# AIR.net
KiCad netlist of a schematic drawn in Altium Designer
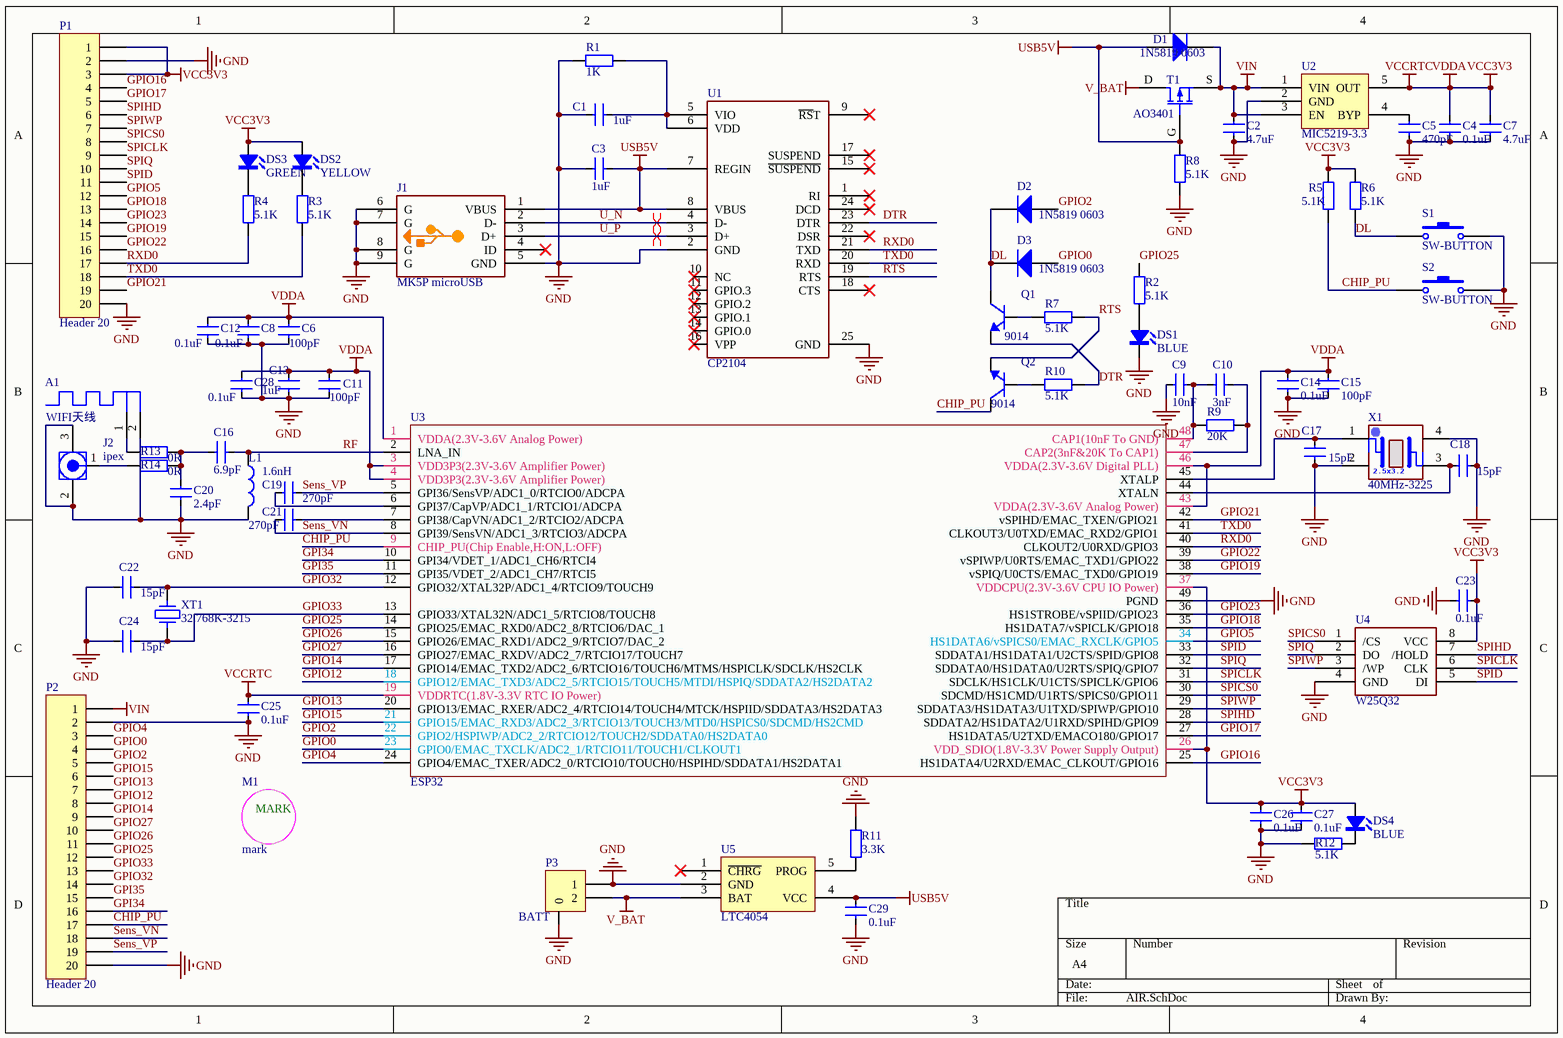
[diagram p0: AIR.SchDoc]

(export (version "E")
  (design (tool "Eeschema 10.0.6"))
  (components
    (comp (ref "A1") (value "WIFI天线") (footprint "2.4G") (libsource (lib "LIB_MANGO") (part "ANT2.4G")))
    (comp (ref "C1")
      (value "1uF")
      (footprint "C0402")
      (description "普通小电容")
      (libsource (lib "LIB_MANGO") (part "CAP"))
    )
    (comp (ref "C2")
      (value "4.7uF")
      (footprint "C0603")
      (description "普通小电容")
      (libsource (lib "LIB_MANGO") (part "CAP"))
    )
    (comp (ref "C3")
      (value "1uF")
      (footprint "C0402")
      (description "普通小电容")
      (libsource (lib "LIB_MANGO") (part "CAP"))
    )
    (comp (ref "C4")
      (value "0.1uF")
      (footprint "C0402")
      (description "普通小电容")
      (libsource (lib "LIB_MANGO") (part "CAP"))
    )
    (comp (ref "C5")
      (value "470pF")
      (footprint "C0402")
      (description "普通小电容")
      (libsource (lib "LIB_MANGO") (part "CAP"))
    )
    (comp (ref "C6")
      (value "100pF")
      (footprint "C0402")
      (description "普通小电容")
      (libsource (lib "LIB_MANGO") (part "CAP"))
    )
    (comp (ref "C7")
      (value "4.7uF")
      (footprint "C0603")
      (description "普通小电容")
      (libsource (lib "LIB_MANGO") (part "CAP"))
    )
    (comp (ref "C8")
      (value "0.1uF")
      (footprint "C0402")
      (description "普通小电容")
      (libsource (lib "LIB_MANGO") (part "CAP"))
    )
    (comp (ref "C9")
      (value "10nF")
      (footprint "C0402")
      (description "普通小电容")
      (libsource (lib "LIB_MANGO") (part "CAP"))
    )
    (comp (ref "C10")
      (value "3nF")
      (footprint "C0402")
      (description "普通小电容")
      (libsource (lib "LIB_MANGO") (part "CAP"))
    )
    (comp (ref "C11")
      (value "100pF")
      (footprint "C0402")
      (description "普通小电容")
      (libsource (lib "LIB_MANGO") (part "CAP"))
    )
    (comp (ref "C12")
      (value "0.1uF")
      (footprint "C0402")
      (description "普通小电容")
      (libsource (lib "LIB_MANGO") (part "CAP"))
    )
    (comp (ref "C13")
      (value "1uF")
      (footprint "C0402")
      (description "普通小电容")
      (libsource (lib "LIB_MANGO") (part "CAP"))
    )
    (comp (ref "C14")
      (value "0.1uF")
      (footprint "C0402")
      (description "普通小电容")
      (libsource (lib "LIB_MANGO") (part "CAP"))
    )
    (comp (ref "C15")
      (value "100pF")
      (footprint "C0402")
      (description "普通小电容")
      (libsource (lib "LIB_MANGO") (part "CAP"))
    )
    (comp (ref "C16")
      (value "6.9pF")
      (footprint "C0402")
      (description "射频电容")
      (libsource (lib "LIB_MANGO") (part "CAP"))
    )
    (comp (ref "C17")
      (value "15pF")
      (footprint "C0402")
      (description "普通小电容")
      (libsource (lib "LIB_MANGO") (part "CAP"))
    )
    (comp (ref "C18")
      (value "15pF")
      (footprint "C0402")
      (description "普通小电容")
      (libsource (lib "LIB_MANGO") (part "CAP"))
    )
    (comp (ref "C19")
      (value "270pF")
      (footprint "C0402")
      (description "普通小电容")
      (libsource (lib "LIB_MANGO") (part "CAP"))
    )
    (comp (ref "C20")
      (value "2.4pF")
      (footprint "C0402")
      (description "射频电容")
      (libsource (lib "LIB_MANGO") (part "CAP"))
    )
    (comp (ref "C21")
      (value "270pF")
      (footprint "C0402")
      (description "普通小电容")
      (libsource (lib "LIB_MANGO") (part "CAP"))
    )
    (comp (ref "C22")
      (value "15pF")
      (footprint "C0402")
      (description "普通小电容")
      (libsource (lib "LIB_MANGO") (part "CAP"))
    )
    (comp (ref "C23")
      (value "0.1uF")
      (footprint "C0402")
      (description "普通小电容")
      (libsource (lib "LIB_MANGO") (part "CAP"))
    )
    (comp (ref "C24")
      (value "15pF")
      (footprint "C0402")
      (description "普通小电容")
      (libsource (lib "LIB_MANGO") (part "CAP"))
    )
    (comp (ref "C25")
      (value "0.1uF")
      (footprint "C0402")
      (description "普通小电容")
      (libsource (lib "LIB_MANGO") (part "CAP"))
    )
    (comp (ref "C26")
      (value "0.1uF")
      (footprint "C0402")
      (description "普通小电容")
      (libsource (lib "LIB_MANGO") (part "CAP"))
    )
    (comp (ref "C27")
      (value "0.1uF")
      (footprint "C0402")
      (description "普通小电容")
      (libsource (lib "LIB_MANGO") (part "CAP"))
    )
    (comp (ref "C28")
      (value "0.1uF")
      (footprint "C0402")
      (description "普通小电容")
      (libsource (lib "LIB_MANGO") (part "CAP"))
    )
    (comp (ref "C29")
      (value "0.1uF")
      (footprint "C0402")
      (description "普通小电容")
      (libsource (lib "LIB_MANGO") (part "CAP"))
    )
    (comp (ref "D1")
      (value "1N5819 0603")
      (footprint "SOD523")
      (description "普通二极管")
      (libsource (lib "LIB_MANGO") (part "Diode"))
    )
    (comp (ref "D2")
      (value "1N5819 0603")
      (footprint "SOD523")
      (description "普通二极管")
      (libsource (lib "LIB_MANGO") (part "Diode"))
    )
    (comp (ref "D3")
      (value "1N5819 0603")
      (footprint "SOD523")
      (description "普通二极管")
      (libsource (lib "LIB_MANGO") (part "Diode"))
    )
    (comp (ref "DS1")
      (value "BLUE")
      (footprint "LED0402")
      (description "LED")
      (libsource (lib "LIB_MANGO") (part "LED"))
    )
    (comp (ref "DS2")
      (value "YELLOW")
      (footprint "LED0402")
      (description "LED")
      (libsource (lib "LIB_MANGO") (part "LED"))
    )
    (comp (ref "DS3")
      (value "GREEN")
      (footprint "LED0402")
      (description "LED")
      (libsource (lib "LIB_MANGO") (part "LED"))
    )
    (comp (ref "DS4")
      (value "BLUE")
      (footprint "LED0402")
      (description "LED")
      (libsource (lib "LIB_MANGO") (part "LED"))
    )
    (comp (ref "J1")
      (value "MK5P microUSB")
      (footprint "MICROUSB")
      (description "4固定脚microUSB座")
      (libsource (lib "A") (part "MICRO_USB"))
    )
    (comp (ref "J2")
      (value "ipex")
      (footprint "I-PEX SOCKET")
      (libsource (lib "LIB_MANGO") (part "MCX_IPEX"))
    )
    (comp (ref "L1")
      (value "1.6nH")
      (footprint "L0402")
      (description "射频电感")
      (libsource (lib "LIB_MANGO") (part "L0402"))
    )
    (comp (ref "M1") (value "mark") (footprint "ZY_UR-3X2") (libsource (lib "LIB_MANGO") (part "mark")))
    (comp (ref "P1")
      (value "Header 20")
      (footprint "HDR1X20-M")
      (description "Header, 20-Pin")
      (fields (field (name "PUBLISHER") "Altium Limited"))
      (libsource (lib "A") (part "Header 20"))
    )
    (comp (ref "P2")
      (value "Header 20")
      (footprint "HDR1X20-M")
      (description "Header, 20-Pin")
      (fields (field (name "PUBLISHER") "Altium Limited"))
      (libsource (lib "A") (part "Header 20"))
    )
    (comp (ref "P3")
      (value "BATT")
      (footprint "PH1.25-T")
      (description "Header, 4-Pin")
      (fields (field (name "PUBLISHER") "Altium Limited"))
      (libsource (lib "LIB_MANGO") (part "Header 2T"))
    )
    (comp (ref "Q1")
      (value "9014")
      (footprint "SOT23")
      (description "NPN三极管")
      (fields (field (name "PUBLISHER") "Altium Limited"))
      (libsource (lib "LIB_MANGO") (part "NPN"))
    )
    (comp (ref "Q2")
      (value "9014")
      (footprint "SOT23")
      (description "NPN三极管")
      (fields (field (name "PUBLISHER") "Altium Limited"))
      (libsource (lib "LIB_MANGO") (part "NPN"))
    )
    (comp (ref "R1")
      (value "1K")
      (footprint "R0402")
      (description "普通电阻")
      (libsource (lib "") (part "RES_2"))
    )
    (comp (ref "R2")
      (value "5.1K")
      (footprint "R0402")
      (description "普通电阻")
      (libsource (lib "LIB_MANGO") (part "RES"))
    )
    (comp (ref "R3")
      (value "5.1K")
      (footprint "R0402")
      (description "普通电阻")
      (libsource (lib "LIB_MANGO") (part "RES"))
    )
    (comp (ref "R4")
      (value "5.1K")
      (footprint "R0402")
      (description "普通电阻")
      (libsource (lib "LIB_MANGO") (part "RES"))
    )
    (comp (ref "R5")
      (value "5.1K")
      (footprint "R0402")
      (description "普通电阻")
      (libsource (lib "") (part "RES_3"))
    )
    (comp (ref "R6")
      (value "5.1K")
      (footprint "R0402")
      (description "普通电阻")
      (libsource (lib "LIB_MANGO") (part "RES"))
    )
    (comp (ref "R7")
      (value "5.1K")
      (footprint "R0402")
      (description "普通电阻")
      (libsource (lib "") (part "RES_1"))
    )
    (comp (ref "R8")
      (value "5.1K")
      (footprint "R0402")
      (description "普通电阻")
      (libsource (lib "LIB_MANGO") (part "RES"))
    )
    (comp (ref "R9")
      (value "20K")
      (footprint "R0402")
      (description "普通电阻")
      (libsource (lib "") (part "RES_1"))
    )
    (comp (ref "R10")
      (value "5.1K")
      (footprint "R0402")
      (description "普通电阻")
      (libsource (lib "") (part "RES_1"))
    )
    (comp (ref "R11")
      (value "3.3K")
      (footprint "R0402")
      (description "普通电阻")
      (libsource (lib "LIB_MANGO") (part "RES"))
    )
    (comp (ref "R12")
      (value "5.1K")
      (footprint "R0402")
      (description "普通电阻")
      (libsource (lib "") (part "RES_1"))
    )
    (comp (ref "R13")
      (value "0R")
      (footprint "R0402")
      (description "普通电阻")
      (libsource (lib "") (part "RES_1"))
    )
    (comp (ref "R14")
      (value "0R")
      (footprint "R0402")
      (description "普通电阻")
      (libsource (lib "") (part "RES_1"))
    )
    (comp (ref "S1")
      (value "SW-BUTTON")
      (footprint "MINIBUTTON")
      (libsource (lib "LIB_MANGO") (part "SW-BUTTON"))
    )
    (comp (ref "S2")
      (value "SW-BUTTON")
      (footprint "MINIBUTTON")
      (libsource (lib "LIB_MANGO") (part "SW-BUTTON"))
    )
    (comp (ref "T1") (value "AO3401") (footprint "SOT23") (libsource (lib "LIB_MANGO") (part "MOS-P")))
    (comp (ref "U1") (value "CP2104") (footprint "QFN24") (libsource (lib "LIB_MANGO") (part "CP2104")))
    (comp (ref "U2")
      (value "MIC5219-3.3")
      (footprint "SOT23-5")
      (libsource (lib "LIB_MANGO") (part "MIC5219"))
    )
    (comp (ref "U3") (value "ESP32") (footprint "QFN40P600X600X100-48N") (libsource (lib "A") (part "ESP32")))
    (comp (ref "U4")
      (value "W25Q32")
      (footprint "WSON-SPIFLASH")
      (libsource (lib "LIB_MANGO") (part "SPIFLASH_SOP8W"))
    )
    (comp (ref "U5")
      (value "LTC4054")
      (footprint "SOT23-5")
      (description "锂电池管理芯片")
      (libsource (lib "LIB_MANGO") (part "LTC4054"))
    )
    (comp (ref "X1")
      (value "40MHz-3225")
      (footprint "XTAL3225")
      (libsource (lib "LIB_MANGO") (part "XTAL3225"))
    )
    (comp (ref "XT1")
      (value "32.768K-3215")
      (footprint "Y3215")
      (description "晶振")
      (libsource (lib "LIB_MANGO") (part "XT"))
    )
  )
  (nets
    (net (code "1") (name "/CHIP_PU") (class "Default")
      (node (ref "P2") (pin "17") (pinfunction "17_17") (pintype "passive"))
      (node (ref "Q2") (pin "C") (pinfunction "C_C") (pintype "passive"))
      (node (ref "R5") (pin "2") (pinfunction "2_2") (pintype "passive"))
      (node (ref "S2") (pin "1") (pinfunction "1_1") (pintype "passive"))
      (node (ref "U3") (pin "9") (pinfunction "CHIP_PU(Chip_Enable,H:ON,L:OFF)_9") (pintype "passive"))
    )
    (net (code "2") (name "/DL") (class "Default")
      (node (ref "D2") (pin "K") (pinfunction "K_K") (pintype "passive"))
      (node (ref "D3") (pin "K") (pinfunction "K_K") (pintype "passive"))
      (node (ref "Q1") (pin "C") (pinfunction "C_C") (pintype "passive"))
      (node (ref "R6") (pin "1") (pinfunction "1_1") (pintype "passive"))
      (node (ref "S1") (pin "1") (pinfunction "1_1") (pintype "passive"))
    )
    (net (code "3") (name "/DTR") (class "Default")
      (node (ref "Q1") (pin "E") (pinfunction "E_E") (pintype "passive"))
      (node (ref "R10") (pin "1") (pinfunction "1_1") (pintype "passive"))
      (node (ref "U1") (pin "23") (pinfunction "DTR_23") (pintype "passive"))
    )
    (net (code "4") (name "/GPI34") (class "Default")
      (node (ref "P2") (pin "16") (pinfunction "16_16") (pintype "passive"))
      (node (ref "U3") (pin "10") (pinfunction "GPI34/VDET_1/ADC1_CH6/RTCI4_10") (pintype "passive"))
    )
    (net (code "5") (name "/GPI35") (class "Default")
      (node (ref "P2") (pin "15") (pinfunction "15_15") (pintype "passive"))
      (node (ref "U3") (pin "11") (pinfunction "GPI35/VDET_2/ADC1_CH7/RTCI5_11") (pintype "passive"))
    )
    (net (code "6") (name "/GPIO0") (class "Default")
      (node (ref "D3") (pin "A") (pinfunction "A_A") (pintype "passive"))
      (node (ref "P2") (pin "4") (pinfunction "4_4") (pintype "passive"))
      (node (ref "U3") (pin "23") (pinfunction "GPIO0/EMAC_TXCLK/ADC2_1/RTCIO11/TOUCH1/CLKOUT1_23") (pintype "passive"))
    )
    (net (code "7") (name "/GPIO2") (class "Default")
      (node (ref "D2") (pin "A") (pinfunction "A_A") (pintype "passive"))
      (node (ref "P2") (pin "5") (pinfunction "5_5") (pintype "passive"))
      (node (ref "U3") (pin "22") (pinfunction "GPIO2/HSPIWP/ADC2_2/RTCIO12/TOUCH2/SDDATA0/HS2DATA0_22") (pintype "passive"))
    )
    (net (code "8") (name "/GPIO4") (class "Default")
      (node (ref "P2") (pin "3") (pinfunction "3_3") (pintype "passive"))
      (node (ref "U3") (pin "24") (pinfunction "GPIO4/EMAC_TXER/ADC2_0/RTCIO10/TOUCH0/HSPIHD/SDDATA1/HS2DATA1_24") (pintype "passive"))
    )
    (net (code "9") (name "/GPIO5") (class "Default")
      (node (ref "P1") (pin "12") (pinfunction "12_12") (pintype "passive"))
      (node (ref "U3") (pin "34") (pinfunction "HS1DATA6/vSPICS0/EMAC_RXCLK/GPIO5_34") (pintype "passive"))
    )
    (net (code "10") (name "/GPIO12") (class "Default")
      (node (ref "P2") (pin "8") (pinfunction "8_8") (pintype "passive"))
      (node (ref "U3") (pin "18") (pinfunction "GPIO12/EMAC_TXD3/ADC2_5/RTCIO15/TOUCH5/MTDI/HSPIQ/SDDATA2/HS2DATA2_18") (pintype "passive"))
    )
    (net (code "11") (name "/GPIO13") (class "Default")
      (node (ref "P2") (pin "7") (pinfunction "7_7") (pintype "passive"))
      (node (ref "U3") (pin "20") (pinfunction "GPIO13/EMAC_RXER/ADC2_4/RTCIO14/TOUCH4/MTCK/HSPIID/SDDATA3/HS2DATA3_20") (pintype "passive"))
    )
    (net (code "12") (name "/GPIO14") (class "Default")
      (node (ref "P2") (pin "9") (pinfunction "9_9") (pintype "passive"))
      (node (ref "U3") (pin "17") (pinfunction "GPIO14/EMAC_TXD2/ADC2_6/RTCIO16/TOUCH6/MTMS/HSPICLK/SDCLK/HS2CLK_17") (pintype "passive"))
    )
    (net (code "13") (name "/GPIO15") (class "Default")
      (node (ref "P2") (pin "6") (pinfunction "6_6") (pintype "passive"))
      (node (ref "U3") (pin "21") (pinfunction "GPIO15/EMAC_RXD3/ADC2_3/RTCIO13/TOUCH3/MTD0/HSPICS0/SDCMD/HS2CMD_21") (pintype "passive"))
    )
    (net (code "14") (name "/GPIO16") (class "Default")
      (node (ref "P1") (pin "4") (pinfunction "4_4") (pintype "passive"))
      (node (ref "U3") (pin "25") (pinfunction "HS1DATA4/U2RXD/EMAC_CLKOUT/GPIO16_25") (pintype "passive"))
    )
    (net (code "15") (name "/GPIO17") (class "Default")
      (node (ref "P1") (pin "5") (pinfunction "5_5") (pintype "passive"))
      (node (ref "U3") (pin "27") (pinfunction "HS1DATA5/U2TXD/EMACO180/GPIO17_27") (pintype "passive"))
    )
    (net (code "16") (name "/GPIO18") (class "Default")
      (node (ref "P1") (pin "13") (pinfunction "13_13") (pintype "passive"))
      (node (ref "U3") (pin "35") (pinfunction "HS1DATA7/vSPICLK/GPIO18_35") (pintype "passive"))
    )
    (net (code "17") (name "/GPIO19") (class "Default")
      (node (ref "P1") (pin "15") (pinfunction "15_15") (pintype "passive"))
      (node (ref "U3") (pin "38") (pinfunction "vSPIQ/U0CTS/EMAC_TXD0/GPIO19_38") (pintype "passive"))
    )
    (net (code "18") (name "/GPIO21") (class "Default")
      (node (ref "P1") (pin "19") (pinfunction "19_19") (pintype "passive"))
      (node (ref "U3") (pin "42") (pinfunction "vSPIHD/EMAC_TXEN/GPIO21_42") (pintype "passive"))
    )
    (net (code "19") (name "/GPIO22") (class "Default")
      (node (ref "P1") (pin "16") (pinfunction "16_16") (pintype "passive"))
      (node (ref "U3") (pin "39") (pinfunction "vSPIWP/U0RTS/EMAC_TXD1/GPIO22_39") (pintype "passive"))
    )
    (net (code "20") (name "/GPIO23") (class "Default")
      (node (ref "P1") (pin "14") (pinfunction "14_14") (pintype "passive"))
      (node (ref "U3") (pin "36") (pinfunction "HS1STROBE/vSPIID/GPIO23_36") (pintype "passive"))
    )
    (net (code "21") (name "/GPIO25") (class "Default")
      (node (ref "P2") (pin "12") (pinfunction "12_12") (pintype "passive"))
      (node (ref "R2") (pin "2") (pinfunction "2_2") (pintype "passive"))
      (node (ref "U3") (pin "14") (pinfunction "GPIO25/EMAC_RXD0/ADC2_8/RTCIO6/DAC_1_14") (pintype "passive"))
    )
    (net (code "22") (name "/GPIO26") (class "Default")
      (node (ref "P2") (pin "11") (pinfunction "11_11") (pintype "passive"))
      (node (ref "U3") (pin "15") (pinfunction "GPIO26/EMAC_RXD1/ADC2_9/RTCIO7/DAC_2_15") (pintype "passive"))
    )
    (net (code "23") (name "/GPIO27") (class "Default")
      (node (ref "P2") (pin "10") (pinfunction "10_10") (pintype "passive"))
      (node (ref "U3") (pin "16") (pinfunction "GPIO27/EMAC_RXDV/ADC2_7/RTCIO17/TOUCH7_16") (pintype "passive"))
    )
    (net (code "24") (name "/GPIO32") (class "Default")
      (node (ref "C22") (pin "2") (pinfunction "2_2") (pintype "passive"))
      (node (ref "P2") (pin "14") (pinfunction "14_14") (pintype "passive"))
      (node (ref "U3") (pin "12") (pinfunction "GPIO32/XTAL32P/ADC1_4/RTCIO9/TOUCH9_12") (pintype "passive"))
      (node (ref "XT1") (pin "2") (pinfunction "2_2") (pintype "passive"))
    )
    (net (code "25") (name "/GPIO33") (class "Default")
      (node (ref "C24") (pin "2") (pinfunction "2_2") (pintype "passive"))
      (node (ref "P2") (pin "13") (pinfunction "13_13") (pintype "passive"))
      (node (ref "U3") (pin "13") (pinfunction "GPIO33/XTAL32N/ADC1_5/RTCIO8/TOUCH8_13") (pintype "passive"))
      (node (ref "XT1") (pin "1") (pinfunction "1_1") (pintype "passive"))
    )
    (net (code "26") (name "/RF") (class "Default")
      (node (ref "C16") (pin "2") (pinfunction "2_2") (pintype "passive"))
      (node (ref "L1") (pin "2") (pinfunction "2_2") (pintype "passive"))
      (node (ref "U3") (pin "2") (pinfunction "LNA_IN_2") (pintype "passive"))
    )
    (net (code "27") (name "/RTS") (class "Default")
      (node (ref "Q2") (pin "E") (pinfunction "E_E") (pintype "passive"))
      (node (ref "R7") (pin "1") (pinfunction "1_1") (pintype "passive"))
      (node (ref "U1") (pin "19") (pinfunction "RTS_19") (pintype "passive"))
    )
    (net (code "28") (name "/RXD0") (class "Default")
      (node (ref "P1") (pin "17") (pinfunction "17_17") (pintype "passive"))
      (node (ref "R4") (pin "1") (pinfunction "1_1") (pintype "passive"))
      (node (ref "U1") (pin "21") (pinfunction "TXD_21") (pintype "passive"))
      (node (ref "U3") (pin "40") (pinfunction "CLKOUT2/U0RXD/GPIO3_40") (pintype "passive"))
    )
    (net (code "29") (name "/SPICLK") (class "Default")
      (node (ref "P1") (pin "9") (pinfunction "9_9") (pintype "passive"))
      (node (ref "U3") (pin "31") (pinfunction "SDCLK/HS1CLK/U1CTS/SPICLK/GPIO6_31") (pintype "passive"))
      (node (ref "U4") (pin "6") (pinfunction "CLK_6") (pintype "passive"))
    )
    (net (code "30") (name "/SPICS0") (class "Default")
      (node (ref "P1") (pin "8") (pinfunction "8_8") (pintype "passive"))
      (node (ref "U3") (pin "30") (pinfunction "SDCMD/HS1CMD/U1RTS/SPICS0/GPIO11_30") (pintype "passive"))
      (node (ref "U4") (pin "1") (pinfunction "/CS_1") (pintype "passive"))
    )
    (net (code "31") (name "/SPID") (class "Default")
      (node (ref "P1") (pin "11") (pinfunction "11_11") (pintype "passive"))
      (node (ref "U3") (pin "33") (pinfunction "SDDATA1/HS1DATA1/U2CTS/SPID/GPIO8_33") (pintype "passive"))
      (node (ref "U4") (pin "5") (pinfunction "DI_5") (pintype "passive"))
    )
    (net (code "32") (name "/SPIHD") (class "Default")
      (node (ref "P1") (pin "6") (pinfunction "6_6") (pintype "passive"))
      (node (ref "U3") (pin "28") (pinfunction "SDDATA2/HS1DATA2/U1RXD/SPIHD/GPIO9_28") (pintype "passive"))
      (node (ref "U4") (pin "7") (pinfunction "/HOLD_7") (pintype "passive"))
    )
    (net (code "33") (name "/SPIQ") (class "Default")
      (node (ref "P1") (pin "10") (pinfunction "10_10") (pintype "passive"))
      (node (ref "U3") (pin "32") (pinfunction "SDDATA0/HS1DATA0/U2RTS/SPIQ/GPIO7_32") (pintype "passive"))
      (node (ref "U4") (pin "2") (pinfunction "DO_2") (pintype "passive"))
    )
    (net (code "34") (name "/SPIWP") (class "Default")
      (node (ref "P1") (pin "7") (pinfunction "7_7") (pintype "passive"))
      (node (ref "U3") (pin "29") (pinfunction "SDDATA3/HS1DATA3/U1TXD/SPIWP/GPIO10_29") (pintype "passive"))
      (node (ref "U4") (pin "3") (pinfunction "/WP_3") (pintype "passive"))
    )
    (net (code "35") (name "/Sens_VN") (class "Default")
      (node (ref "C21") (pin "1") (pinfunction "1_1") (pintype "passive"))
      (node (ref "P2") (pin "18") (pinfunction "18_18") (pintype "passive"))
      (node (ref "U3") (pin "8") (pinfunction "GPI39/SensVN/ADC1_3/RTCIO3/ADCPA_8") (pintype "passive"))
    )
    (net (code "36") (name "/Sens_VP") (class "Default")
      (node (ref "C19") (pin "2") (pinfunction "2_2") (pintype "passive"))
      (node (ref "P2") (pin "19") (pinfunction "19_19") (pintype "passive"))
      (node (ref "U3") (pin "5") (pinfunction "GPI36/SensVP/ADC1_0/RTCIO0/ADCPA_5") (pintype "passive"))
    )
    (net (code "37") (name "/TXD0") (class "Default")
      (node (ref "P1") (pin "18") (pinfunction "18_18") (pintype "passive"))
      (node (ref "R3") (pin "1") (pinfunction "1_1") (pintype "passive"))
      (node (ref "U1") (pin "20") (pinfunction "RXD_20") (pintype "passive"))
      (node (ref "U3") (pin "41") (pinfunction "CLKOUT3/U0TXD/EMAC_RXD2/GPIO1_41") (pintype "passive"))
    )
    (net (code "38") (name "/U_N") (class "Default")
      (node (ref "J1") (pin "2") (pinfunction "D-_2") (pintype "passive"))
      (node (ref "U1") (pin "4") (pinfunction "D-_4") (pintype "passive"))
    )
    (net (code "39") (name "/U_P") (class "Default")
      (node (ref "J1") (pin "3") (pinfunction "D+_3") (pintype "passive"))
      (node (ref "U1") (pin "3") (pinfunction "D+_3") (pintype "passive"))
    )
    (net (code "40") (name "GND") (class "Default")
      (node (ref "A1") (pin "2") (pinfunction "G_2") (pintype "passive"))
      (node (ref "C1") (pin "2") (pinfunction "2_2") (pintype "passive"))
      (node (ref "C11") (pin "1") (pinfunction "1_1") (pintype "passive"))
      (node (ref "C12") (pin "1") (pinfunction "1_1") (pintype "passive"))
      (node (ref "C13") (pin "1") (pinfunction "1_1") (pintype "passive"))
      (node (ref "C14") (pin "1") (pinfunction "1_1") (pintype "passive"))
      (node (ref "C15") (pin "1") (pinfunction "1_1") (pintype "passive"))
      (node (ref "C17") (pin "2") (pinfunction "2_2") (pintype "passive"))
      (node (ref "C18") (pin "2") (pinfunction "2_2") (pintype "passive"))
      (node (ref "C2") (pin "1") (pinfunction "1_1") (pintype "passive"))
      (node (ref "C20") (pin "1") (pinfunction "1_1") (pintype "passive"))
      (node (ref "C22") (pin "1") (pinfunction "1_1") (pintype "passive"))
      (node (ref "C23") (pin "2") (pinfunction "2_2") (pintype "passive"))
      (node (ref "C24") (pin "1") (pinfunction "1_1") (pintype "passive"))
      (node (ref "C25") (pin "1") (pinfunction "1_1") (pintype "passive"))
      (node (ref "C26") (pin "1") (pinfunction "1_1") (pintype "passive"))
      (node (ref "C27") (pin "1") (pinfunction "1_1") (pintype "passive"))
      (node (ref "C28") (pin "1") (pinfunction "1_1") (pintype "passive"))
      (node (ref "C29") (pin "1") (pinfunction "1_1") (pintype "passive"))
      (node (ref "C3") (pin "1") (pinfunction "1_1") (pintype "passive"))
      (node (ref "C4") (pin "1") (pinfunction "1_1") (pintype "passive"))
      (node (ref "C5") (pin "2") (pinfunction "2_2") (pintype "passive"))
      (node (ref "C6") (pin "1") (pinfunction "1_1") (pintype "passive"))
      (node (ref "C7") (pin "1") (pinfunction "1_1") (pintype "passive"))
      (node (ref "C8") (pin "1") (pinfunction "1_1") (pintype "passive"))
      (node (ref "C9") (pin "2") (pinfunction "2_2") (pintype "passive"))
      (node (ref "DS1") (pin "K") (pinfunction "2_K") (pintype "passive"))
      (node (ref "J1") (pin "5") (pinfunction "GND_5") (pintype "power_in"))
      (node (ref "J1") (pin "6") (pinfunction "G_6") (pintype "passive"))
      (node (ref "J1") (pin "7") (pinfunction "G_7") (pintype "passive"))
      (node (ref "J1") (pin "8") (pinfunction "G_8") (pintype "passive"))
      (node (ref "J1") (pin "9") (pinfunction "G_9") (pintype "passive"))
      (node (ref "J2") (pin "2") (pinfunction "GND_2") (pintype "power_in"))
      (node (ref "J2") (pin "3") (pinfunction "GND_3") (pintype "power_in"))
      (node (ref "L1") (pin "1") (pinfunction "1_1") (pintype "passive"))
      (node (ref "P1") (pin "2") (pinfunction "2_2") (pintype "passive"))
      (node (ref "P1") (pin "20") (pinfunction "20_20") (pintype "passive"))
      (node (ref "P2") (pin "2") (pinfunction "2_2") (pintype "passive"))
      (node (ref "P2") (pin "20") (pinfunction "20_20") (pintype "passive"))
      (node (ref "P3") (pin "0") (pinfunction "0_0") (pintype "passive"))
      (node (ref "P3") (pin "1") (pinfunction "1_1") (pintype "passive"))
      (node (ref "R1") (pin "1") (pinfunction "1_1") (pintype "passive"))
      (node (ref "R11") (pin "2") (pinfunction "2_2") (pintype "passive"))
      (node (ref "R12") (pin "2") (pinfunction "2_2") (pintype "passive"))
      (node (ref "R8") (pin "1") (pinfunction "1_1") (pintype "passive"))
      (node (ref "S1") (pin "2") (pinfunction "2_2") (pintype "passive"))
      (node (ref "S2") (pin "2") (pinfunction "2_2") (pintype "passive"))
      (node (ref "U1") (pin "2") (pinfunction "GND_2") (pintype "power_in"))
      (node (ref "U1") (pin "25") (pinfunction "GND_25") (pintype "power_in"))
      (node (ref "U2") (pin "2") (pinfunction "GND_2") (pintype "passive"))
      (node (ref "U3") (pin "49") (pinfunction "PGND_49") (pintype "passive"))
      (node (ref "U4") (pin "4") (pinfunction "GND_4") (pintype "passive"))
      (node (ref "U5") (pin "2") (pinfunction "GND_2") (pintype "passive"))
      (node (ref "X1") (pin "2") (pinfunction "NC1_2") (pintype "passive"))
      (node (ref "X1") (pin "4") (pinfunction "NC2_4") (pintype "passive"))
    )
    (net (code "41") (name "Net-(A1-Pad1)") (class "Default")
      (node (ref "A1") (pin "1") (pintype "passive"))
      (node (ref "R13") (pin "2") (pinfunction "2_2") (pintype "passive"))
    )
    (net (code "42") (name "Net-(C16-Pad1)") (class "Default")
      (node (ref "C16") (pin "1") (pinfunction "1_1") (pintype "passive"))
      (node (ref "C20") (pin "2") (pinfunction "2_2") (pintype "passive"))
      (node (ref "R13") (pin "1") (pinfunction "1_1") (pintype "passive"))
      (node (ref "R14") (pin "1") (pinfunction "1_1") (pintype "passive"))
    )
    (net (code "43") (name "Net-(DS1-1)") (class "Default")
      (node (ref "DS1") (pin "A") (pinfunction "1_A") (pintype "passive"))
      (node (ref "R2") (pin "1") (pinfunction "1_1") (pintype "passive"))
    )
    (net (code "44") (name "Net-(DS2-2)") (class "Default")
      (node (ref "DS2") (pin "K") (pinfunction "2_K") (pintype "passive"))
      (node (ref "R3") (pin "2") (pinfunction "2_2") (pintype "passive"))
    )
    (net (code "45") (name "Net-(DS3-2)") (class "Default")
      (node (ref "DS3") (pin "K") (pinfunction "2_K") (pintype "passive"))
      (node (ref "R4") (pin "2") (pinfunction "2_2") (pintype "passive"))
    )
    (net (code "46") (name "Net-(DS4-2)") (class "Default")
      (node (ref "DS4") (pin "K") (pinfunction "2_K") (pintype "passive"))
      (node (ref "R12") (pin "1") (pinfunction "1_1") (pintype "passive"))
    )
    (net (code "47") (name "Net-(J2-Signal)") (class "Default")
      (node (ref "J2") (pin "1") (pinfunction "Signal_1") (pintype "passive"))
      (node (ref "R14") (pin "2") (pinfunction "2_2") (pintype "passive"))
    )
    (net (code "48") (name "Net-(Q1-PadB)") (class "Default")
      (node (ref "Q1") (pin "B") (pinfunction "B_B") (pintype "passive"))
      (node (ref "R7") (pin "2") (pinfunction "2_2") (pintype "passive"))
    )
    (net (code "49") (name "Net-(Q2-PadB)") (class "Default")
      (node (ref "Q2") (pin "B") (pinfunction "B_B") (pintype "passive"))
      (node (ref "R10") (pin "2") (pinfunction "2_2") (pintype "passive"))
    )
    (net (code "50") (name "Net-(U1-VDD)") (class "Default")
      (node (ref "C1") (pin "1") (pinfunction "1_1") (pintype "passive"))
      (node (ref "R1") (pin "2") (pinfunction "2_2") (pintype "passive"))
      (node (ref "U1") (pin "5") (pinfunction "VIO_5") (pintype "passive"))
      (node (ref "U1") (pin "6") (pinfunction "VDD_6") (pintype "passive"))
    )
    (net (code "51") (name "Net-(U2-BYP)") (class "Default")
      (node (ref "C5") (pin "1") (pinfunction "1_1") (pintype "passive"))
      (node (ref "U2") (pin "4") (pinfunction "BYP_4") (pintype "passive"))
    )
    (net (code "52") (name "Net-(U3-CAP1(10nF_To_GND))") (class "Default")
      (node (ref "C10") (pin "2") (pinfunction "2_2") (pintype "passive"))
      (node (ref "C9") (pin "1") (pinfunction "1_1") (pintype "passive"))
      (node (ref "R9") (pin "2") (pinfunction "2_2") (pintype "passive"))
      (node (ref "U3") (pin "48") (pinfunction "CAP1(10nF_To_GND)_48") (pintype "passive"))
    )
    (net (code "53") (name "Net-(U3-CAP2(3nF&20K_To_CAP1))") (class "Default")
      (node (ref "C10") (pin "1") (pinfunction "1_1") (pintype "passive"))
      (node (ref "R9") (pin "1") (pinfunction "1_1") (pintype "passive"))
      (node (ref "U3") (pin "47") (pinfunction "CAP2(3nF&20K_To_CAP1)_47") (pintype "passive"))
    )
    (net (code "54") (name "Net-(U3-GPI37{slash}CapVP{slash}ADC1_1{slash}RTCIO1{slash}ADCPA)") (class "Default")
      (node (ref "C19") (pin "1") (pinfunction "1_1") (pintype "passive"))
      (node (ref "U3") (pin "6") (pinfunction "GPI37/CapVP/ADC1_1/RTCIO1/ADCPA_6") (pintype "passive"))
    )
    (net (code "55") (name "Net-(U3-GPI38{slash}CapVN{slash}ADC1_2{slash}RTCIO2{slash}ADCPA)") (class "Default")
      (node (ref "C21") (pin "2") (pinfunction "2_2") (pintype "passive"))
      (node (ref "U3") (pin "7") (pinfunction "GPI38/CapVN/ADC1_2/RTCIO2/ADCPA_7") (pintype "passive"))
    )
    (net (code "56") (name "Net-(U3-XTALN)") (class "Default")
      (node (ref "C18") (pin "1") (pinfunction "1_1") (pintype "passive"))
      (node (ref "U3") (pin "44") (pinfunction "XTALN_44") (pintype "passive"))
      (node (ref "X1") (pin "3") (pinfunction "X2_3") (pintype "passive"))
    )
    (net (code "57") (name "Net-(U3-XTALP)") (class "Default")
      (node (ref "C17") (pin "1") (pinfunction "1_1") (pintype "passive"))
      (node (ref "U3") (pin "45") (pinfunction "XTALP_45") (pintype "passive"))
      (node (ref "X1") (pin "1") (pinfunction "X1_1") (pintype "passive"))
    )
    (net (code "58") (name "Net-(U5-PROG)") (class "Default")
      (node (ref "R11") (pin "1") (pinfunction "1_1") (pintype "passive"))
      (node (ref "U5") (pin "5") (pinfunction "PROG_5") (pintype "passive"))
    )
    (net (code "59") (name "USB5V") (class "Default")
      (node (ref "C29") (pin "2") (pinfunction "2_2") (pintype "passive"))
      (node (ref "C3") (pin "2") (pinfunction "2_2") (pintype "passive"))
      (node (ref "D1") (pin "A") (pinfunction "A_A") (pintype "passive"))
      (node (ref "J1") (pin "1") (pinfunction "VBUS_1") (pintype "power_in"))
      (node (ref "R8") (pin "2") (pinfunction "2_2") (pintype "passive"))
      (node (ref "T1") (pin "G") (pinfunction "G_G") (pintype "passive"))
      (node (ref "U1") (pin "7") (pinfunction "REGIN_7") (pintype "passive"))
      (node (ref "U1") (pin "8") (pinfunction "VBUS_8") (pintype "power_in"))
      (node (ref "U5") (pin "4") (pinfunction "VCC_4") (pintype "passive"))
    )
    (net (code "60") (name "VCC3V3") (class "Default")
      (node (ref "C11") (pin "2") (pinfunction "2_2") (pintype "passive"))
      (node (ref "C12") (pin "2") (pinfunction "2_2") (pintype "passive"))
      (node (ref "C13") (pin "2") (pinfunction "2_2") (pintype "passive"))
      (node (ref "C14") (pin "2") (pinfunction "2_2") (pintype "passive"))
      (node (ref "C15") (pin "2") (pinfunction "2_2") (pintype "passive"))
      (node (ref "C23") (pin "1") (pinfunction "1_1") (pintype "passive"))
      (node (ref "C25") (pin "2") (pinfunction "2_2") (pintype "passive"))
      (node (ref "C26") (pin "2") (pinfunction "2_2") (pintype "passive"))
      (node (ref "C27") (pin "2") (pinfunction "2_2") (pintype "passive"))
      (node (ref "C28") (pin "2") (pinfunction "2_2") (pintype "passive"))
      (node (ref "C4") (pin "2") (pinfunction "2_2") (pintype "passive"))
      (node (ref "C6") (pin "2") (pinfunction "2_2") (pintype "passive"))
      (node (ref "C7") (pin "2") (pinfunction "2_2") (pintype "passive"))
      (node (ref "C8") (pin "2") (pinfunction "2_2") (pintype "passive"))
      (node (ref "DS2") (pin "A") (pinfunction "1_A") (pintype "passive"))
      (node (ref "DS3") (pin "A") (pinfunction "1_A") (pintype "passive"))
      (node (ref "DS4") (pin "A") (pinfunction "1_A") (pintype "passive"))
      (node (ref "P1") (pin "1") (pinfunction "1_1") (pintype "passive"))
      (node (ref "P1") (pin "3") (pinfunction "3_3") (pintype "passive"))
      (node (ref "R5") (pin "1") (pinfunction "1_1") (pintype "passive"))
      (node (ref "R6") (pin "2") (pinfunction "2_2") (pintype "passive"))
      (node (ref "U2") (pin "5") (pinfunction "OUT_5") (pintype "passive"))
      (node (ref "U3") (pin "1") (pinfunction "VDDA(2.3V-3.6V_Analog_Power)_1") (pintype "passive"))
      (node (ref "U3") (pin "19") (pinfunction "VDDRTC(1.8V-3.3V_RTC_IO_Power)_19") (pintype "passive"))
      (node (ref "U3") (pin "26") (pinfunction "VDD_SDIO(1.8V-3.3V_Power_Supply_Output)_26") (pintype "passive"))
      (node (ref "U3") (pin "3") (pinfunction "VDD3P3(2.3V-3.6V_Amplifier_Power)_3") (pintype "passive"))
      (node (ref "U3") (pin "37") (pinfunction "VDDCPU(2.3V-3.6V_CPU_IO_Power)_37") (pintype "passive"))
      (node (ref "U3") (pin "4") (pinfunction "VDD3P3(2.3V-3.6V_Amplifier_Power)_4") (pintype "passive"))
      (node (ref "U3") (pin "43") (pinfunction "VDDA(2.3V-3.6V_Analog_Power)_43") (pintype "passive"))
      (node (ref "U3") (pin "46") (pinfunction "VDDA(2.3V-3.6V_Digital_PLL)_46") (pintype "passive"))
      (node (ref "U4") (pin "8") (pinfunction "VCC_8") (pintype "passive"))
    )
    (net (code "61") (name "VIN") (class "Default")
      (node (ref "C2") (pin "2") (pinfunction "2_2") (pintype "passive"))
      (node (ref "D1") (pin "K") (pinfunction "K_K") (pintype "passive"))
      (node (ref "P2") (pin "1") (pinfunction "1_1") (pintype "passive"))
      (node (ref "T1") (pin "S") (pinfunction "S_S") (pintype "passive"))
      (node (ref "U2") (pin "1") (pinfunction "VIN_1") (pintype "passive"))
      (node (ref "U2") (pin "3") (pinfunction "EN_3") (pintype "passive"))
    )
    (net (code "62") (name "V_BAT") (class "Default")
      (node (ref "P3") (pin "2") (pinfunction "2_2") (pintype "passive"))
      (node (ref "T1") (pin "D") (pinfunction "D_D") (pintype "passive"))
      (node (ref "U5") (pin "3") (pinfunction "BAT_3") (pintype "passive"))
    )
    (net (code "63") (name "unconnected-(J1-ID-Pad4)") (class "Default")
      (node (ref "J1") (pin "4") (pinfunction "ID_4") (pintype "passive+no_connect"))
    )
    (net (code "64") (name "unconnected-(U1-CTS-Pad18)") (class "Default")
      (node (ref "U1") (pin "18") (pinfunction "CTS_18") (pintype "passive+no_connect"))
    )
    (net (code "65") (name "unconnected-(U1-DCD-Pad24)") (class "Default")
      (node (ref "U1") (pin "24") (pinfunction "DCD_24") (pintype "passive+no_connect"))
    )
    (net (code "66") (name "unconnected-(U1-DSR-Pad22)") (class "Default")
      (node (ref "U1") (pin "22") (pinfunction "DSR_22") (pintype "passive+no_connect"))
    )
    (net (code "67") (name "unconnected-(U1-GPIO.0-Pad14)") (class "Default")
      (node (ref "U1") (pin "14") (pinfunction "GPIO.0_14") (pintype "passive+no_connect"))
    )
    (net (code "68") (name "unconnected-(U1-GPIO.1-Pad13)") (class "Default")
      (node (ref "U1") (pin "13") (pinfunction "GPIO.1_13") (pintype "passive+no_connect"))
    )
    (net (code "69") (name "unconnected-(U1-GPIO.2-Pad12)") (class "Default")
      (node (ref "U1") (pin "12") (pinfunction "GPIO.2_12") (pintype "passive+no_connect"))
    )
    (net (code "70") (name "unconnected-(U1-GPIO.3-Pad11)") (class "Default")
      (node (ref "U1") (pin "11") (pinfunction "GPIO.3_11") (pintype "passive+no_connect"))
    )
    (net (code "71") (name "unconnected-(U1-NC-Pad10)") (class "Default")
      (node (ref "U1") (pin "10") (pinfunction "NC_10") (pintype "passive+no_connect"))
    )
    (net (code "72") (name "unconnected-(U1-RI-Pad1)") (class "Default")
      (node (ref "U1") (pin "1") (pinfunction "RI_1") (pintype "passive+no_connect"))
    )
    (net (code "73") (name "unconnected-(U1-SUSPEND-Pad17)") (class "Default")
      (node (ref "U1") (pin "17") (pinfunction "SUSPEND_17") (pintype "passive+no_connect"))
    )
    (net (code "74") (name "unconnected-(U1-VPP-Pad16)") (class "Default")
      (node (ref "U1") (pin "16") (pinfunction "VPP_16") (pintype "passive+no_connect"))
    )
    (net (code "75") (name "unconnected-(U1-~{RS}T-Pad9)") (class "Default")
      (node (ref "U1") (pin "9") (pinfunction "~{RS}T_9") (pintype "passive+no_connect"))
    )
    (net (code "76") (name "unconnected-(U1-~{SUSPEND}-Pad15)") (class "Default")
      (node (ref "U1") (pin "15") (pinfunction "~{SUSPEND}_15") (pintype "passive+no_connect"))
    )
    (net (code "77") (name "unconnected-(U5-~{CHRG}-Pad1)") (class "Default")
      (node (ref "U5") (pin "1") (pinfunction "~{CHRG}_1") (pintype "passive+no_connect"))
    )
  )
)
